# mcp3008-breakout.net
KiCad netlist of a schematic drawn in EAGLE
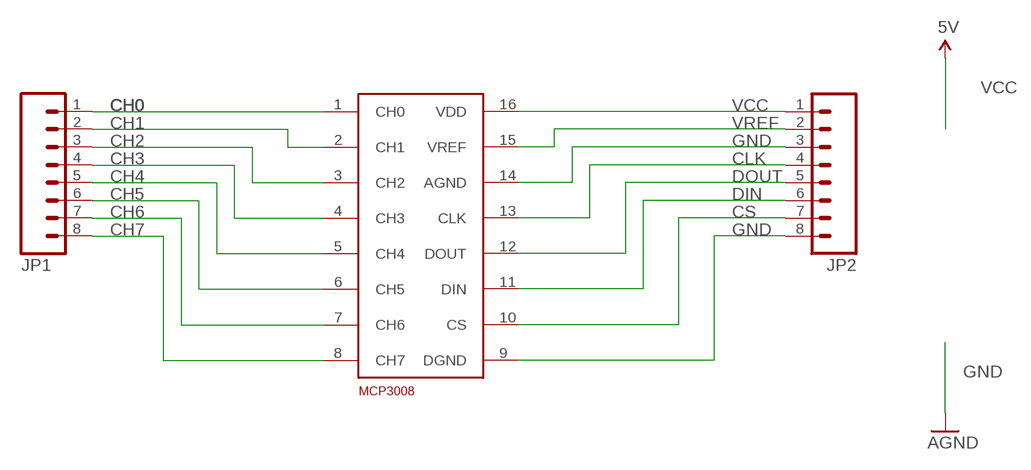
[diagram p0: schematic, sheet 1]

(export (version "E")
  (design (tool "Eeschema 10.0.6"))
  (components
    (comp (ref "JP1")
      (value "M081X08")
      (footprint "eagle-import:1X08")
      (libsource (lib "eagle-import") (part "M081X08"))
    )
    (comp (ref "JP2")
      (value "M081X08")
      (footprint "eagle-import:1X08")
      (libsource (lib "eagle-import") (part "M081X08"))
    )
    (comp (ref "U1")
      (value "MCP3008")
      (footprint "eagle-import:SOIC16N")
      (libsource (lib "eagle-import") (part "MCP3008"))
    )
  )
  (nets
    (net (code "1") (name "/CH0") (class "Default")
      (node (ref "JP1") (pin "1") (pinfunction "1_1") (pintype "passive"))
      (node (ref "U1") (pin "1") (pinfunction "CH0_1") (pintype "bidirectional"))
    )
    (net (code "2") (name "/CH1") (class "Default")
      (node (ref "JP1") (pin "2") (pinfunction "2_2") (pintype "passive"))
      (node (ref "U1") (pin "2") (pinfunction "CH1_2") (pintype "bidirectional"))
    )
    (net (code "3") (name "/CH2") (class "Default")
      (node (ref "JP1") (pin "3") (pinfunction "3_3") (pintype "passive"))
      (node (ref "U1") (pin "3") (pinfunction "CH2_3") (pintype "bidirectional"))
    )
    (net (code "4") (name "/CH3") (class "Default")
      (node (ref "JP1") (pin "4") (pinfunction "4_4") (pintype "passive"))
      (node (ref "U1") (pin "4") (pinfunction "CH3_4") (pintype "bidirectional"))
    )
    (net (code "5") (name "/CH4") (class "Default")
      (node (ref "JP1") (pin "5") (pinfunction "5_5") (pintype "passive"))
      (node (ref "U1") (pin "5") (pinfunction "CH4_5") (pintype "bidirectional"))
    )
    (net (code "6") (name "/CH5") (class "Default")
      (node (ref "JP1") (pin "6") (pinfunction "6_6") (pintype "passive"))
      (node (ref "U1") (pin "6") (pinfunction "CH5_6") (pintype "bidirectional"))
    )
    (net (code "7") (name "/CH6") (class "Default")
      (node (ref "JP1") (pin "7") (pinfunction "7_7") (pintype "passive"))
      (node (ref "U1") (pin "7") (pinfunction "CH6_7") (pintype "bidirectional"))
    )
    (net (code "8") (name "/CH7") (class "Default")
      (node (ref "JP1") (pin "8") (pinfunction "8_8") (pintype "passive"))
      (node (ref "U1") (pin "8") (pinfunction "CH7_8") (pintype "bidirectional"))
    )
    (net (code "9") (name "/CLK") (class "Default")
      (node (ref "JP2") (pin "4") (pinfunction "4_4") (pintype "passive"))
      (node (ref "U1") (pin "13") (pinfunction "CLK_13") (pintype "bidirectional"))
    )
    (net (code "10") (name "/CS") (class "Default")
      (node (ref "JP2") (pin "7") (pinfunction "7_7") (pintype "passive"))
      (node (ref "U1") (pin "10") (pinfunction "CS_10") (pintype "bidirectional"))
    )
    (net (code "11") (name "/DIN") (class "Default")
      (node (ref "JP2") (pin "6") (pinfunction "6_6") (pintype "passive"))
      (node (ref "U1") (pin "11") (pinfunction "DIN_11") (pintype "bidirectional"))
    )
    (net (code "12") (name "/DOUT") (class "Default")
      (node (ref "JP2") (pin "5") (pinfunction "5_5") (pintype "passive"))
      (node (ref "U1") (pin "12") (pinfunction "DOUT_12") (pintype "bidirectional"))
    )
    (net (code "13") (name "/VREF") (class "Default")
      (node (ref "JP2") (pin "2") (pinfunction "2_2") (pintype "passive"))
      (node (ref "U1") (pin "15") (pinfunction "VREF_15") (pintype "bidirectional"))
    )
    (net (code "14") (name "5V") (class "Default")
      (node (ref "JP2") (pin "1") (pinfunction "1_1") (pintype "passive"))
      (node (ref "U1") (pin "16") (pinfunction "VDD_16") (pintype "bidirectional"))
    )
    (net (code "15") (name "AGND") (class "Default")
      (node (ref "JP2") (pin "3") (pinfunction "3_3") (pintype "passive"))
      (node (ref "JP2") (pin "8") (pinfunction "8_8") (pintype "passive"))
      (node (ref "U1") (pin "14") (pinfunction "AGND_14") (pintype "bidirectional"))
      (node (ref "U1") (pin "9") (pinfunction "DGND_9") (pintype "bidirectional"))
    )
  )
)
